# Power.net
KiCad netlist of a schematic drawn in Altium Designer
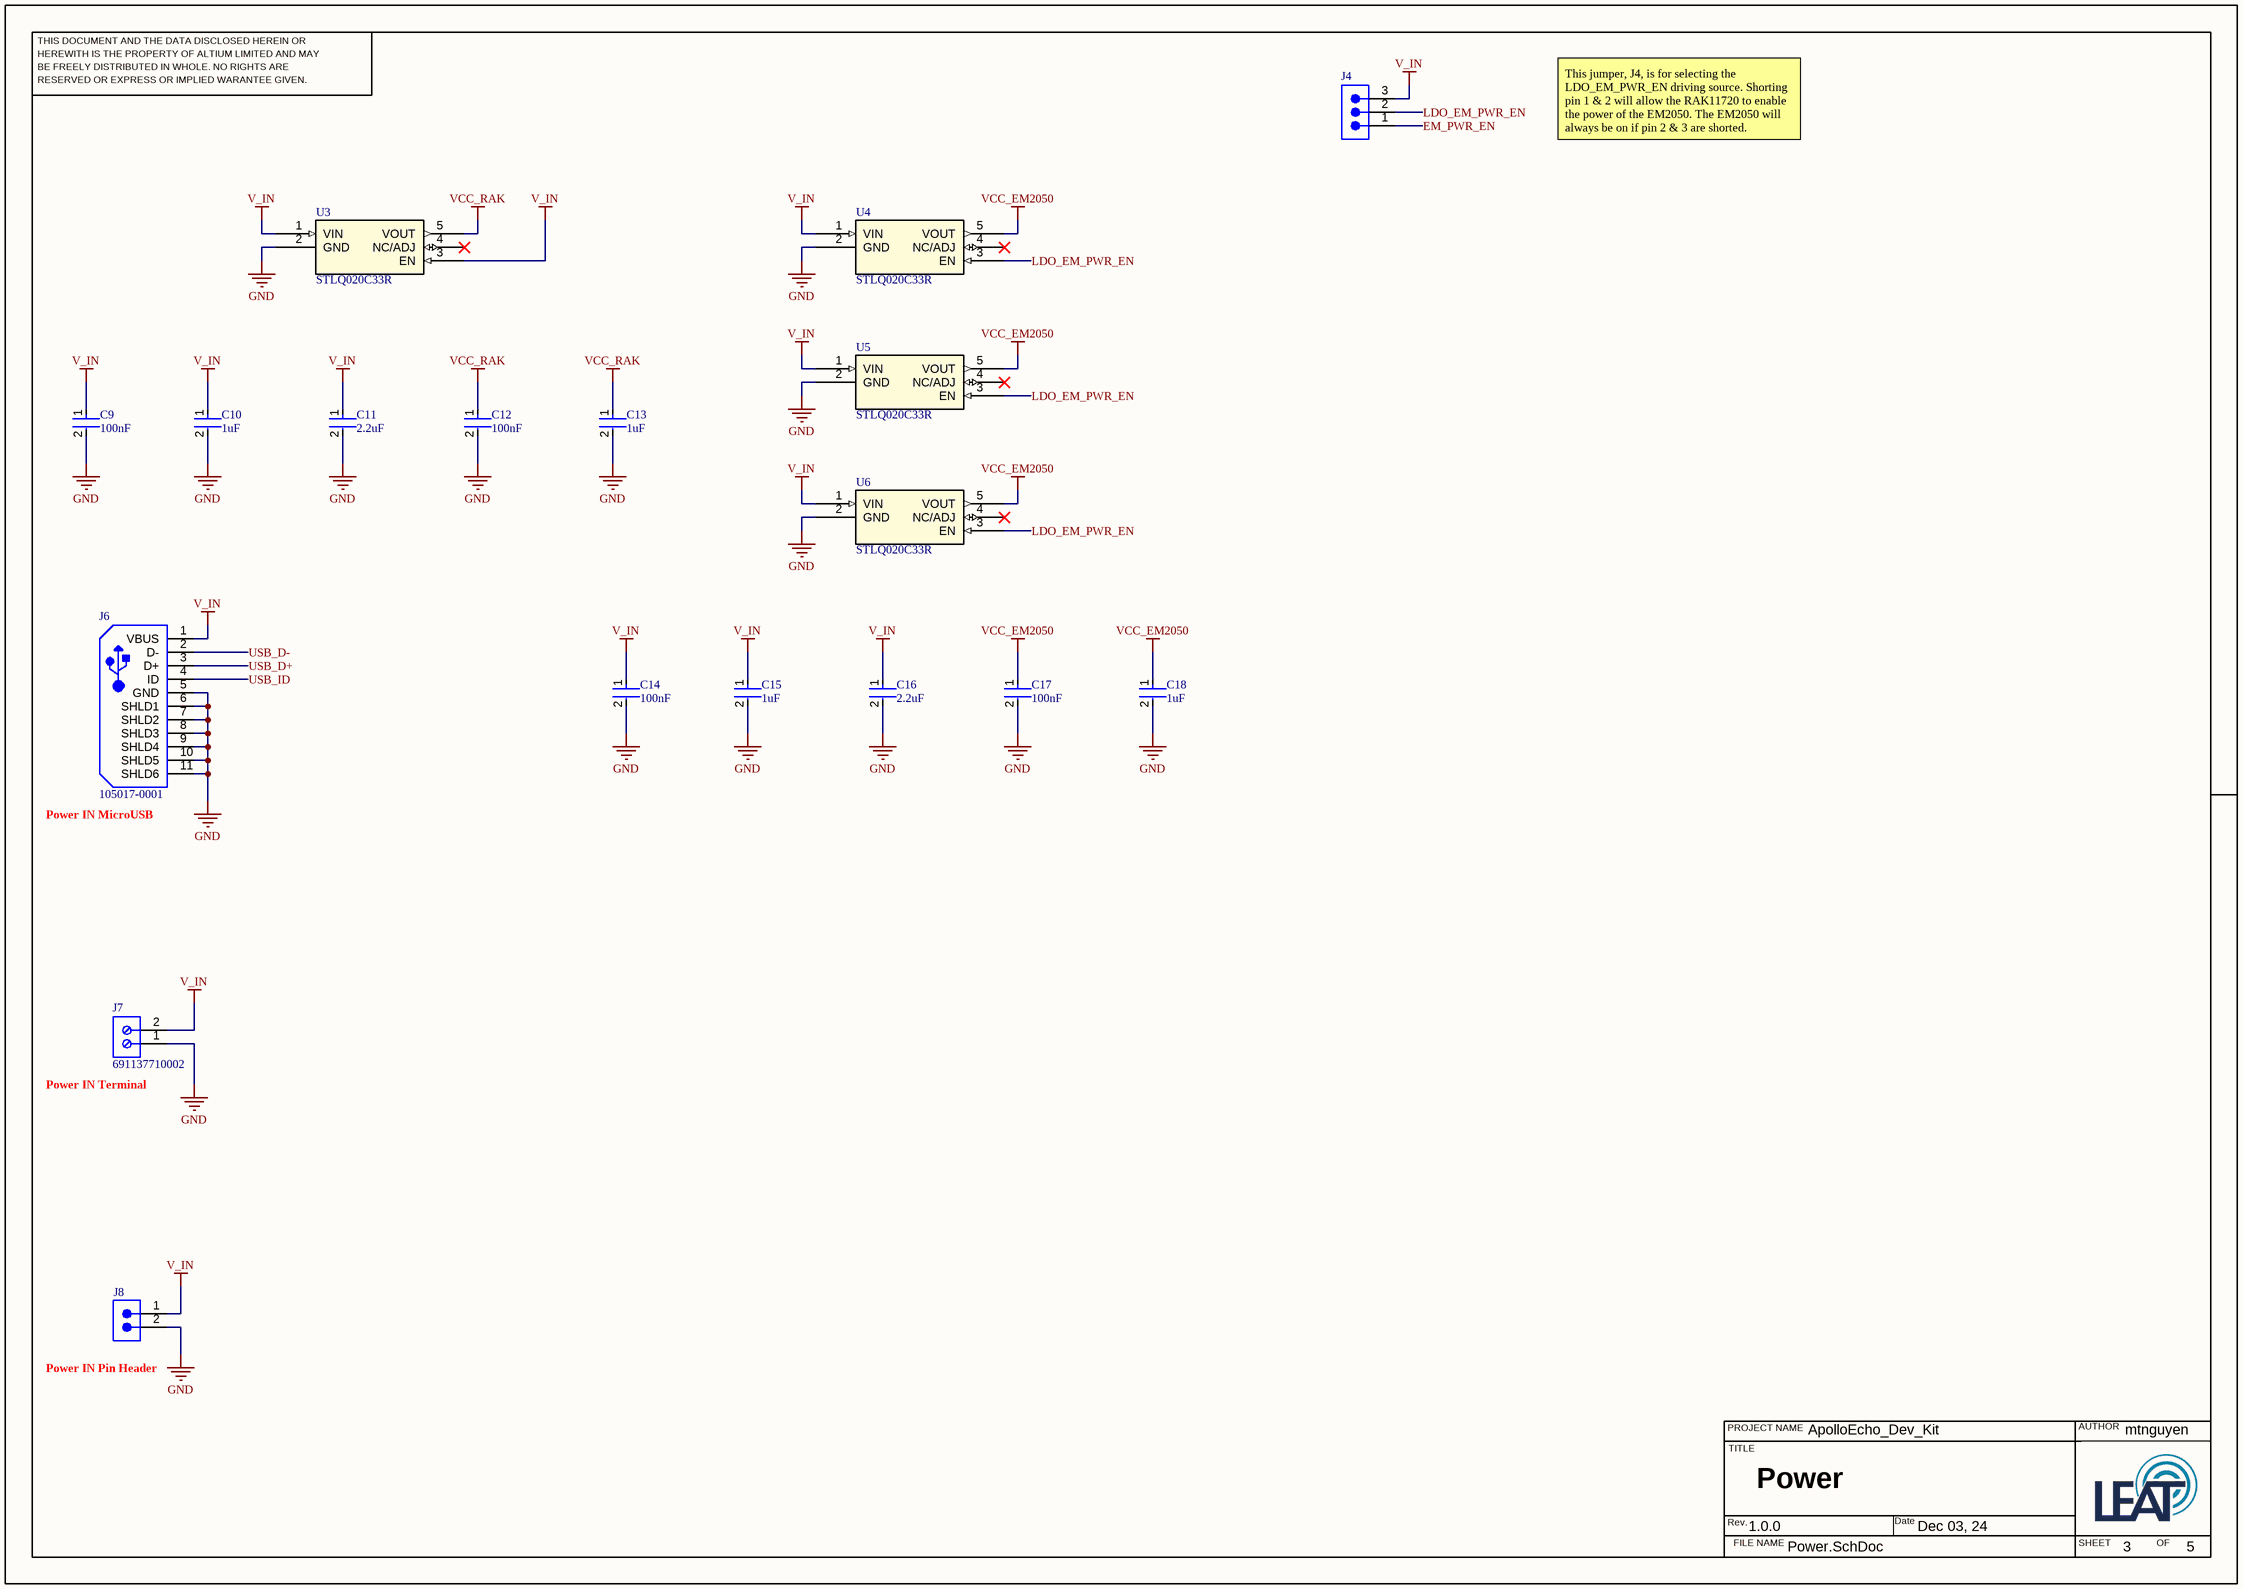
[diagram p0: Power.SchDoc]

(export (version "E")
  (design (tool "Eeschema 10.0.6"))
  (components
    (comp (ref "C9")
      (value "0402ZD104KAT2A")
      (footprint "FP-0402-L_1_0_1-W_0_5_0_1-IPC_C")
      (description "General Purpose Ceramic Capacitor, 0402, 100nF, 10%, X5R, 15%, 10V")
      (fields
        (field (name "VOLTAGE") "10V")
        (field (name "TOLERANCE") "10%")
        (field (name "CAPACITANCE") "100nF")
      )
      (libsource (lib "Altium Content Vault") (part "b4654b650e69147ec39a6b967a45e02"))
    )
    (comp (ref "C10")
      (value "EMK105BJ105KV-F")
      (footprint "FP-0402-L_1_0_0_05-W_0_5-IPC_A")
      (description "None")
      (fields (field (name "TOLERANCE") "10%") (field (name "CAPACITANCE") "1uF"))
      (libsource (lib "Altium Content Vault") (part "b4654b650e69147ec39a6b967a45e02"))
    )
    (comp (ref "C11")
      (value "C1005X5R1A225K050BC")
      (footprint "FP-C1005-050-0_05-IPC_A")
      (description "Multilayer Ceramic Capacitors 2.2μF ±10% 10V X5R SMD 0402")
      (fields
        (field (name "TOLERANCE") "10%")
        (field (name "VOLTAGE") "10V")
        (field (name "CAPACITANCE") "2.2uF")
      )
      (libsource (lib "Altium Content Vault") (part "b4654b650e69147ec39a6b967a45e02"))
    )
    (comp (ref "C12")
      (value "0402ZD104KAT2A")
      (footprint "FP-0402-L_1_0_1-W_0_5_0_1-IPC_C")
      (description "General Purpose Ceramic Capacitor, 0402, 100nF, 10%, X5R, 15%, 10V")
      (fields
        (field (name "VOLTAGE") "10V")
        (field (name "TOLERANCE") "10%")
        (field (name "CAPACITANCE") "100nF")
      )
      (libsource (lib "Altium Content Vault") (part "b4654b650e69147ec39a6b967a45e02"))
    )
    (comp (ref "C13")
      (value "EMK105BJ105KV-F")
      (footprint "FP-0402-L_1_0_0_05-W_0_5-IPC_A")
      (description "None")
      (fields (field (name "TOLERANCE") "10%") (field (name "CAPACITANCE") "1uF"))
      (libsource (lib "Altium Content Vault") (part "b4654b650e69147ec39a6b967a45e02"))
    )
    (comp (ref "C14")
      (value "0402ZD104KAT2A")
      (footprint "FP-0402-L_1_0_1-W_0_5_0_1-IPC_C")
      (description "General Purpose Ceramic Capacitor, 0402, 100nF, 10%, X5R, 15%, 10V")
      (fields
        (field (name "VOLTAGE") "10V")
        (field (name "TOLERANCE") "10%")
        (field (name "CAPACITANCE") "100nF")
      )
      (libsource (lib "Altium Content Vault") (part "b4654b650e69147ec39a6b967a45e02"))
    )
    (comp (ref "C15")
      (value "EMK105BJ105KV-F")
      (footprint "FP-0402-L_1_0_0_05-W_0_5-IPC_A")
      (description "None")
      (fields (field (name "TOLERANCE") "10%") (field (name "CAPACITANCE") "1uF"))
      (libsource (lib "Altium Content Vault") (part "b4654b650e69147ec39a6b967a45e02"))
    )
    (comp (ref "C16")
      (value "C1005X5R1A225K050BC")
      (footprint "FP-C1005-050-0_05-IPC_A")
      (description "Multilayer Ceramic Capacitors 2.2μF ±10% 10V X5R SMD 0402")
      (fields
        (field (name "TOLERANCE") "10%")
        (field (name "VOLTAGE") "10V")
        (field (name "CAPACITANCE") "2.2uF")
      )
      (libsource (lib "Altium Content Vault") (part "b4654b650e69147ec39a6b967a45e02"))
    )
    (comp (ref "C17")
      (value "0402ZD104KAT2A")
      (footprint "FP-0402-L_1_0_1-W_0_5_0_1-IPC_C")
      (description "General Purpose Ceramic Capacitor, 0402, 100nF, 10%, X5R, 15%, 10V")
      (fields
        (field (name "VOLTAGE") "10V")
        (field (name "TOLERANCE") "10%")
        (field (name "CAPACITANCE") "100nF")
      )
      (libsource (lib "Altium Content Vault") (part "b4654b650e69147ec39a6b967a45e02"))
    )
    (comp (ref "C18")
      (value "EMK105BJ105KV-F")
      (footprint "FP-0402-L_1_0_0_05-W_0_5-IPC_A")
      (description "None")
      (fields (field (name "TOLERANCE") "10%") (field (name "CAPACITANCE") "1uF"))
      (libsource (lib "Altium Content Vault") (part "b4654b650e69147ec39a6b967a45e02"))
    )
    (comp (ref "J4")
      (value "61300311121")
      (footprint "61300311121")
      (libsource (lib "Altium Content Vault") (part "Header_Male_1R_03P"))
    )
    (comp (ref "J6")
      (value "105017-0001")
      (footprint "USB-MICRO-B_V")
      (fields (field (name "MANUFACTURER") "Molex"))
      (libsource (lib "Altium Content Vault") (part "USB-5-6SHLD"))
    )
    (comp (ref "J7")
      (value "691137710002")
      (footprint "691137710002")
      (libsource (lib "Altium Content Vault") (part "TBL - 1R - 02P - Screw"))
    )
    (comp (ref "J8")
      (value "61300211121")
      (footprint "61300211121")
      (libsource (lib "Altium Content Vault") (part "Header_Male_1R_02P"))
    )
    (comp (ref "U3")
      (value "STLQ020C33R")
      (footprint "SOT323-5L_STM")
      (description "No Description Available")
      (fields (field (name "COPYRIGHT") "Copyright (C) 2023 Ultra Librarian. All rights reserved."))
      (libsource (lib "EchoStar") (part "STLQ020C33R"))
    )
    (comp (ref "U4")
      (value "STLQ020C33R")
      (footprint "SOT323-5L_STM")
      (description "No Description Available")
      (fields (field (name "COPYRIGHT") "Copyright (C) 2023 Ultra Librarian. All rights reserved."))
      (libsource (lib "EchoStar") (part "STLQ020C33R"))
    )
    (comp (ref "U5")
      (value "STLQ020C33R")
      (footprint "SOT323-5L_STM")
      (description "No Description Available")
      (fields (field (name "COPYRIGHT") "Copyright (C) 2023 Ultra Librarian. All rights reserved."))
      (libsource (lib "EchoStar") (part "STLQ020C33R"))
    )
    (comp (ref "U6")
      (value "STLQ020C33R")
      (footprint "SOT323-5L_STM")
      (description "No Description Available")
      (fields (field (name "COPYRIGHT") "Copyright (C) 2023 Ultra Librarian. All rights reserved."))
      (libsource (lib "EchoStar") (part "STLQ020C33R"))
    )
  )
  (nets
    (net (code "1") (name "/EM_PWR_EN") (class "Default")
      (node (ref "J4") (pin "1") (pinfunction "1_1") (pintype "passive"))
    )
    (net (code "2") (name "/LDO_EM_PWR_EN") (class "Default")
      (node (ref "J4") (pin "2") (pinfunction "2_2") (pintype "passive"))
      (node (ref "U4") (pin "3") (pinfunction "EN_3") (pintype "input"))
      (node (ref "U5") (pin "3") (pinfunction "EN_3") (pintype "input"))
      (node (ref "U6") (pin "3") (pinfunction "EN_3") (pintype "input"))
    )
    (net (code "3") (name "/USB_D+") (class "Default")
      (node (ref "J6") (pin "3") (pinfunction "D+_3") (pintype "passive"))
    )
    (net (code "4") (name "/USB_D-") (class "Default")
      (node (ref "J6") (pin "2") (pinfunction "D-_2") (pintype "passive"))
    )
    (net (code "5") (name "/USB_ID") (class "Default")
      (node (ref "J6") (pin "4") (pinfunction "ID_4") (pintype "passive"))
    )
    (net (code "6") (name "GND") (class "Default")
      (node (ref "C10") (pin "2") (pinfunction "2_2") (pintype "passive"))
      (node (ref "C11") (pin "2") (pinfunction "2_2") (pintype "passive"))
      (node (ref "C12") (pin "2") (pinfunction "2_2") (pintype "passive"))
      (node (ref "C13") (pin "2") (pinfunction "2_2") (pintype "passive"))
      (node (ref "C14") (pin "2") (pinfunction "2_2") (pintype "passive"))
      (node (ref "C15") (pin "2") (pinfunction "2_2") (pintype "passive"))
      (node (ref "C16") (pin "2") (pinfunction "2_2") (pintype "passive"))
      (node (ref "C17") (pin "2") (pinfunction "2_2") (pintype "passive"))
      (node (ref "C18") (pin "2") (pinfunction "2_2") (pintype "passive"))
      (node (ref "C9") (pin "2") (pinfunction "2_2") (pintype "passive"))
      (node (ref "J6") (pin "10") (pinfunction "SHLD5_10") (pintype "passive"))
      (node (ref "J6") (pin "11") (pinfunction "SHLD6_11") (pintype "passive"))
      (node (ref "J6") (pin "5") (pinfunction "GND_5") (pintype "passive"))
      (node (ref "J6") (pin "6") (pinfunction "SHLD1_6") (pintype "passive"))
      (node (ref "J6") (pin "7") (pinfunction "SHLD2_7") (pintype "passive"))
      (node (ref "J6") (pin "8") (pinfunction "SHLD3_8") (pintype "passive"))
      (node (ref "J6") (pin "9") (pinfunction "SHLD4_9") (pintype "passive"))
      (node (ref "J7") (pin "1") (pinfunction "1_1") (pintype "passive"))
      (node (ref "J8") (pin "2") (pinfunction "2_2") (pintype "passive"))
      (node (ref "U3") (pin "2") (pinfunction "GND_2") (pintype "power_in"))
      (node (ref "U4") (pin "2") (pinfunction "GND_2") (pintype "power_in"))
      (node (ref "U5") (pin "2") (pinfunction "GND_2") (pintype "power_in"))
      (node (ref "U6") (pin "2") (pinfunction "GND_2") (pintype "power_in"))
    )
    (net (code "7") (name "VCC_EM2050") (class "Default")
      (node (ref "C17") (pin "1") (pinfunction "1_1") (pintype "passive"))
      (node (ref "C18") (pin "1") (pinfunction "1_1") (pintype "passive"))
      (node (ref "U4") (pin "5") (pinfunction "VOUT_5") (pintype "output"))
      (node (ref "U5") (pin "5") (pinfunction "VOUT_5") (pintype "output"))
      (node (ref "U6") (pin "5") (pinfunction "VOUT_5") (pintype "output"))
    )
    (net (code "8") (name "VCC_RAK") (class "Default")
      (node (ref "C12") (pin "1") (pinfunction "1_1") (pintype "passive"))
      (node (ref "C13") (pin "1") (pinfunction "1_1") (pintype "passive"))
      (node (ref "U3") (pin "5") (pinfunction "VOUT_5") (pintype "output"))
    )
    (net (code "9") (name "V_IN") (class "Default")
      (node (ref "C10") (pin "1") (pinfunction "1_1") (pintype "passive"))
      (node (ref "C11") (pin "1") (pinfunction "1_1") (pintype "passive"))
      (node (ref "C14") (pin "1") (pinfunction "1_1") (pintype "passive"))
      (node (ref "C15") (pin "1") (pinfunction "1_1") (pintype "passive"))
      (node (ref "C16") (pin "1") (pinfunction "1_1") (pintype "passive"))
      (node (ref "C9") (pin "1") (pinfunction "1_1") (pintype "passive"))
      (node (ref "J4") (pin "3") (pinfunction "3_3") (pintype "passive"))
      (node (ref "J6") (pin "1") (pinfunction "VBUS_1") (pintype "passive"))
      (node (ref "J7") (pin "2") (pinfunction "2_2") (pintype "passive"))
      (node (ref "J8") (pin "1") (pinfunction "1_1") (pintype "passive"))
      (node (ref "U3") (pin "1") (pinfunction "VIN_1") (pintype "input"))
      (node (ref "U3") (pin "3") (pinfunction "EN_3") (pintype "input"))
      (node (ref "U4") (pin "1") (pinfunction "VIN_1") (pintype "input"))
      (node (ref "U5") (pin "1") (pinfunction "VIN_1") (pintype "input"))
      (node (ref "U6") (pin "1") (pinfunction "VIN_1") (pintype "input"))
    )
    (net (code "10") (name "unconnected-(U3-NC{slash}ADJ-Pad4)") (class "Default")
      (node (ref "U3") (pin "4") (pinfunction "NC/ADJ_4") (pintype "bidirectional+no_connect"))
    )
    (net (code "11") (name "unconnected-(U4-NC{slash}ADJ-Pad4)") (class "Default")
      (node (ref "U4") (pin "4") (pinfunction "NC/ADJ_4") (pintype "bidirectional+no_connect"))
    )
    (net (code "12") (name "unconnected-(U5-NC{slash}ADJ-Pad4)") (class "Default")
      (node (ref "U5") (pin "4") (pinfunction "NC/ADJ_4") (pintype "bidirectional+no_connect"))
    )
    (net (code "13") (name "unconnected-(U6-NC{slash}ADJ-Pad4)") (class "Default")
      (node (ref "U6") (pin "4") (pinfunction "NC/ADJ_4") (pintype "bidirectional+no_connect"))
    )
  )
)
